# STELLA_RF.net
KiCad netlist of a schematic drawn in EAGLE
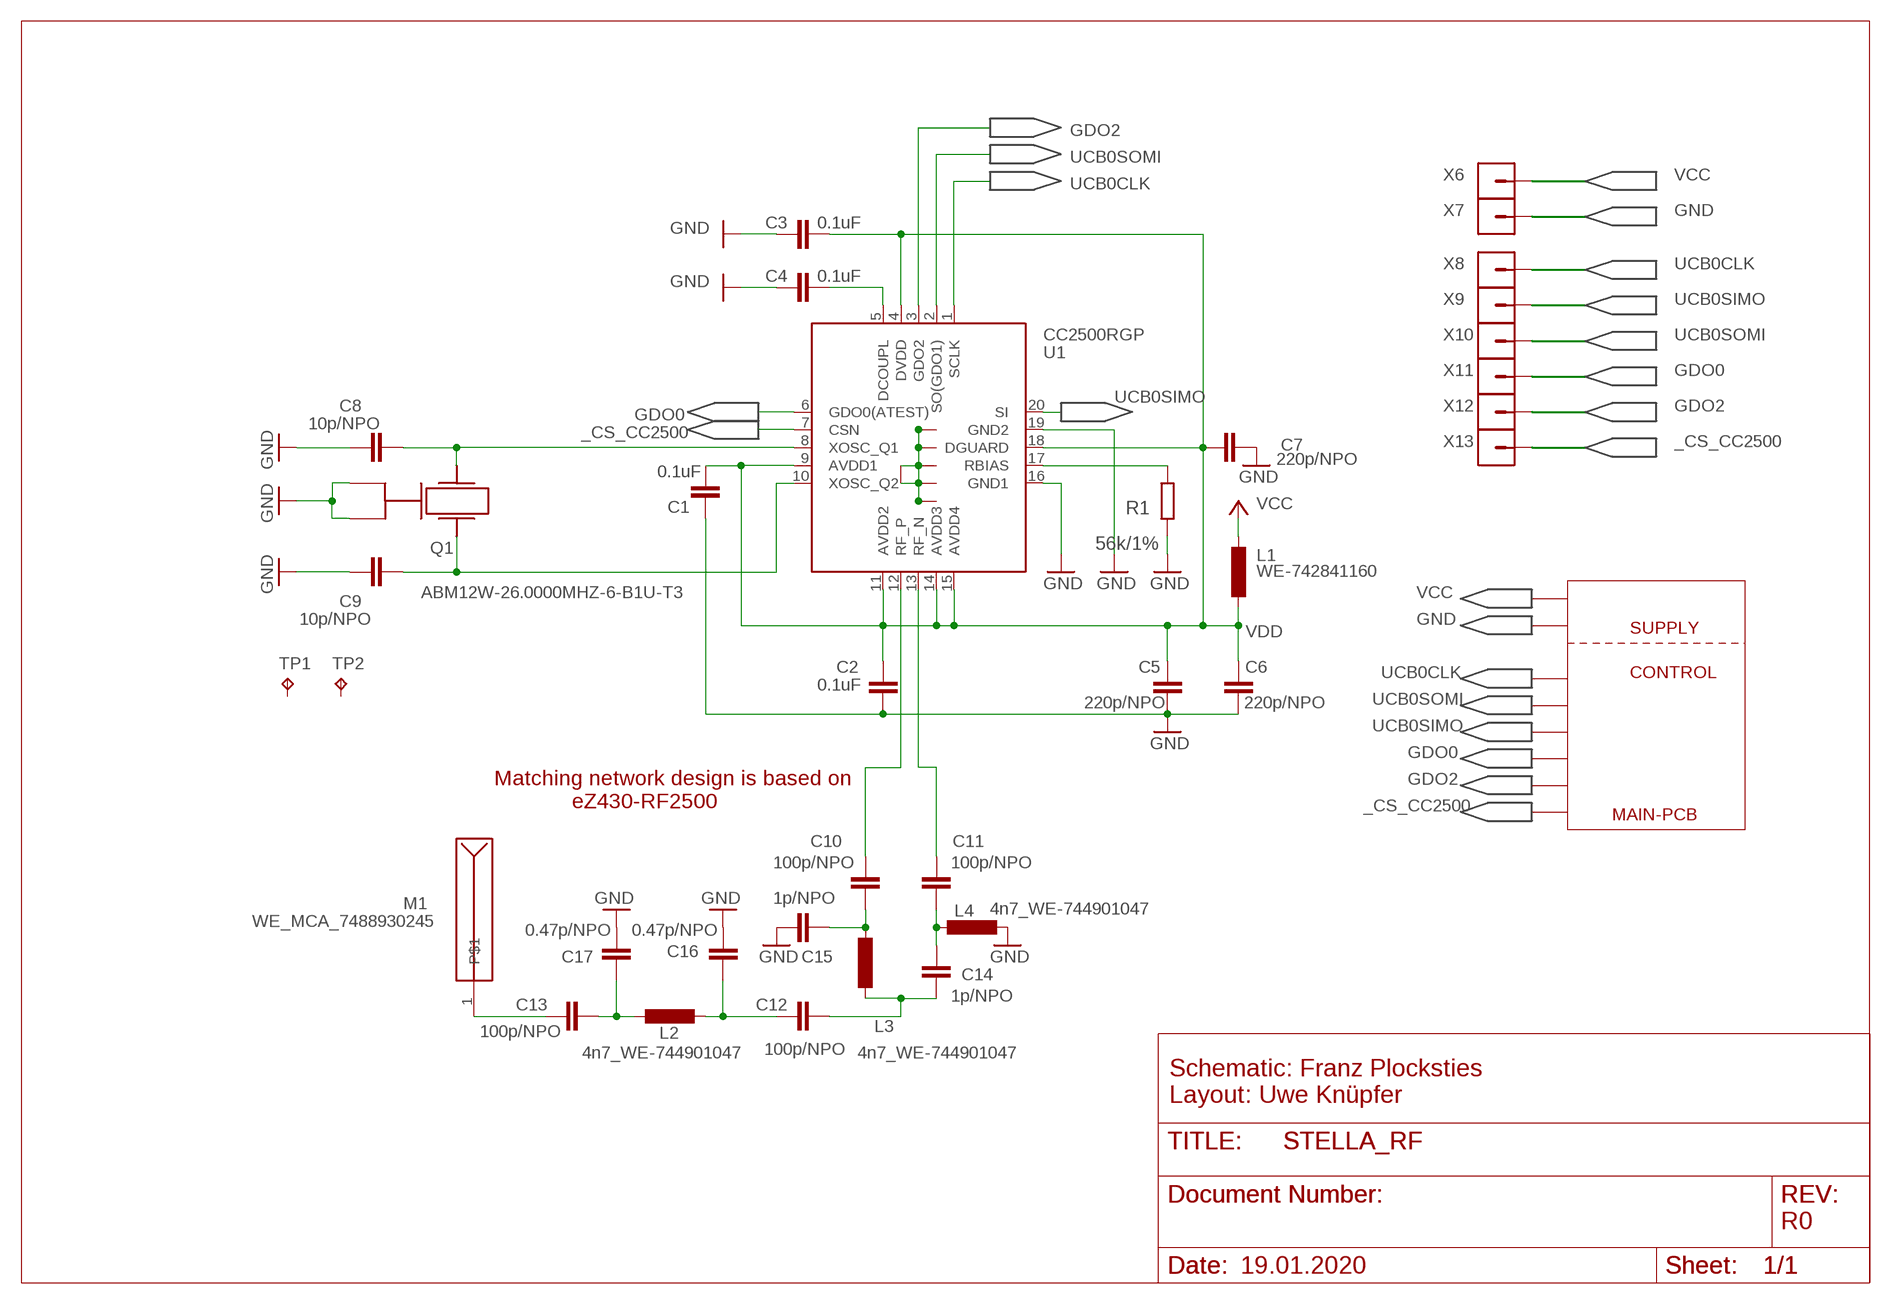
[diagram p0: schematic, sheet 1]

(export (version "E")
  (design (tool "Eeschema 10.0.6"))
  (components
    (comp (ref "C1")
      (value "0.1uF")
      (footprint "eagle-import:C0402")
      (libsource (lib "eagle-import") (part "C-EUC0402"))
    )
    (comp (ref "C2")
      (value "0.1uF")
      (footprint "eagle-import:C0402")
      (libsource (lib "eagle-import") (part "C-EUC0402"))
    )
    (comp (ref "C3")
      (value "0.1uF")
      (footprint "eagle-import:C0402")
      (libsource (lib "eagle-import") (part "C-EUC0402"))
    )
    (comp (ref "C4")
      (value "0.1uF")
      (footprint "eagle-import:C0402")
      (libsource (lib "eagle-import") (part "C-EUC0402"))
    )
    (comp (ref "C5")
      (value "220p/NPO")
      (footprint "eagle-import:C0402")
      (libsource (lib "eagle-import") (part "C-EUC0402"))
    )
    (comp (ref "C6")
      (value "220p/NPO")
      (footprint "eagle-import:C0402")
      (libsource (lib "eagle-import") (part "C-EUC0402"))
    )
    (comp (ref "C7")
      (value "220p/NPO")
      (footprint "eagle-import:C0402")
      (libsource (lib "eagle-import") (part "C-EUC0402"))
    )
    (comp (ref "C8")
      (value "10p/NPO")
      (footprint "eagle-import:C0402")
      (libsource (lib "eagle-import") (part "C-EUC0402"))
    )
    (comp (ref "C9")
      (value "10p/NPO")
      (footprint "eagle-import:C0402")
      (libsource (lib "eagle-import") (part "C-EUC0402"))
    )
    (comp (ref "C10")
      (value "100p/NPO")
      (footprint "eagle-import:C0402")
      (libsource (lib "eagle-import") (part "C-EUC0402"))
    )
    (comp (ref "C11")
      (value "100p/NPO")
      (footprint "eagle-import:C0402")
      (libsource (lib "eagle-import") (part "C-EUC0402"))
    )
    (comp (ref "C12")
      (value "100p/NPO")
      (footprint "eagle-import:C0402")
      (libsource (lib "eagle-import") (part "C-EUC0402"))
    )
    (comp (ref "C13")
      (value "100p/NPO")
      (footprint "eagle-import:C0402")
      (libsource (lib "eagle-import") (part "C-EUC0402"))
    )
    (comp (ref "C14")
      (value "1p/NPO")
      (footprint "eagle-import:C0402")
      (libsource (lib "eagle-import") (part "C-EUC0402"))
    )
    (comp (ref "C15")
      (value "1p/NPO")
      (footprint "eagle-import:C0402")
      (libsource (lib "eagle-import") (part "C-EUC0402"))
    )
    (comp (ref "C16")
      (value "0.47p/NPO")
      (footprint "eagle-import:C0402")
      (libsource (lib "eagle-import") (part "C-EUC0402"))
    )
    (comp (ref "C17")
      (value "0.47p/NPO")
      (footprint "eagle-import:C0402")
      (libsource (lib "eagle-import") (part "C-EUC0402"))
    )
    (comp (ref "L1")
      (value "WE-742841160")
      (footprint "eagle-import:L0402")
      (libsource (lib "eagle-import") (part "L-EU"))
    )
    (comp (ref "L2")
      (value "4n7_WE-744901047")
      (footprint "eagle-import:L0402")
      (libsource (lib "eagle-import") (part "L-EU"))
    )
    (comp (ref "L3")
      (value "4n7_WE-744901047")
      (footprint "eagle-import:L0402")
      (libsource (lib "eagle-import") (part "L-EU"))
    )
    (comp (ref "L4")
      (value "4n7_WE-744901047")
      (footprint "eagle-import:L0402")
      (libsource (lib "eagle-import") (part "L-EU"))
    )
    (comp (ref "M1")
      (value "WE_MCA_7488930245")
      (footprint "eagle-import:WE_MCA_7488930245")
      (libsource (lib "eagle-import") (part "WE_MCA_7488930245"))
    )
    (comp (ref "Q1")
      (value "ABM12W-26.0000MHZ-6-B1U-T3")
      (footprint "eagle-import:ABM12W")
      (libsource (lib "eagle-import") (part "ABM12W"))
    )
    (comp (ref "R1")
      (value "56k/1%")
      (footprint "eagle-import:R0402")
      (libsource (lib "eagle-import") (part "R-EU_R0402"))
    )
    (comp (ref "TP1")
      (value "TPTP06SQ")
      (footprint "eagle-import:TP06SQ")
      (libsource (lib "eagle-import") (part "TPTP06SQ"))
    )
    (comp (ref "TP2")
      (value "TPTP06SQ")
      (footprint "eagle-import:TP06SQ")
      (libsource (lib "eagle-import") (part "TPTP06SQ"))
    )
    (comp (ref "U1")
      (value "CC2500RGP")
      (footprint "eagle-import:CHIPCON_QLP20")
      (libsource (lib "eagle-import") (part "CHIPCON_CC1100"))
    )
    (comp (ref "X6")
      (value "1PIN_INTERFACE")
      (footprint "eagle-import:1PIN_INTERFACE")
      (libsource (lib "eagle-import") (part "1PIN_INTERFACE"))
    )
    (comp (ref "X7")
      (value "1PIN_INTERFACE")
      (footprint "eagle-import:1PIN_INTERFACE")
      (libsource (lib "eagle-import") (part "1PIN_INTERFACE"))
    )
    (comp (ref "X8")
      (value "1PIN_INTERFACE")
      (footprint "eagle-import:1PIN_INTERFACE")
      (libsource (lib "eagle-import") (part "1PIN_INTERFACE"))
    )
    (comp (ref "X9")
      (value "1PIN_INTERFACE")
      (footprint "eagle-import:1PIN_INTERFACE")
      (libsource (lib "eagle-import") (part "1PIN_INTERFACE"))
    )
    (comp (ref "X10")
      (value "1PIN_INTERFACE")
      (footprint "eagle-import:1PIN_INTERFACE")
      (libsource (lib "eagle-import") (part "1PIN_INTERFACE"))
    )
    (comp (ref "X11")
      (value "1PIN_INTERFACE")
      (footprint "eagle-import:1PIN_INTERFACE")
      (libsource (lib "eagle-import") (part "1PIN_INTERFACE"))
    )
    (comp (ref "X12")
      (value "1PIN_INTERFACE")
      (footprint "eagle-import:1PIN_INTERFACE")
      (libsource (lib "eagle-import") (part "1PIN_INTERFACE"))
    )
    (comp (ref "X13")
      (value "1PIN_INTERFACE")
      (footprint "eagle-import:1PIN_INTERFACE")
      (libsource (lib "eagle-import") (part "1PIN_INTERFACE"))
    )
  )
  (nets
    (net (code "1") (name "/GDO0") (class "Default")
      (node (ref "U1") (pin "6") (pinfunction "GDO0(ATEST)_6") (pintype "bidirectional"))
      (node (ref "X11") (pin "1") (pinfunction "1_1") (pintype "bidirectional"))
    )
    (net (code "2") (name "/GDO2") (class "Default")
      (node (ref "U1") (pin "3") (pinfunction "GDO2_3") (pintype "bidirectional"))
      (node (ref "X12") (pin "1") (pinfunction "1_1") (pintype "bidirectional"))
    )
    (net (code "3") (name "/UCB0CLK") (class "Default")
      (node (ref "U1") (pin "1") (pinfunction "SCLK_1") (pintype "bidirectional"))
      (node (ref "X8") (pin "1") (pinfunction "1_1") (pintype "bidirectional"))
    )
    (net (code "4") (name "/UCB0SIMO") (class "Default")
      (node (ref "U1") (pin "20") (pinfunction "SI_20") (pintype "bidirectional"))
      (node (ref "X9") (pin "1") (pinfunction "1_1") (pintype "bidirectional"))
    )
    (net (code "5") (name "/UCB0SOMI") (class "Default")
      (node (ref "U1") (pin "2") (pinfunction "SO(GDO1)_2") (pintype "bidirectional"))
      (node (ref "X10") (pin "1") (pinfunction "1_1") (pintype "bidirectional"))
    )
    (net (code "6") (name "/VDD") (class "Default")
      (node (ref "C1") (pin "2") (pinfunction "2_2") (pintype "passive"))
      (node (ref "C2") (pin "2") (pinfunction "2_2") (pintype "passive"))
      (node (ref "C3") (pin "2") (pinfunction "2_2") (pintype "passive"))
      (node (ref "C5") (pin "2") (pinfunction "2_2") (pintype "passive"))
      (node (ref "C6") (pin "2") (pinfunction "2_2") (pintype "passive"))
      (node (ref "C7") (pin "1") (pinfunction "1_1") (pintype "passive"))
      (node (ref "L1") (pin "2") (pinfunction "2_2") (pintype "passive"))
      (node (ref "U1") (pin "11") (pinfunction "AVDD2_11") (pintype "bidirectional"))
      (node (ref "U1") (pin "14") (pinfunction "AVDD3_14") (pintype "bidirectional"))
      (node (ref "U1") (pin "15") (pinfunction "AVDD4_15") (pintype "bidirectional"))
      (node (ref "U1") (pin "18") (pinfunction "DGUARD_18") (pintype "bidirectional"))
      (node (ref "U1") (pin "4") (pinfunction "DVDD_4") (pintype "bidirectional"))
      (node (ref "U1") (pin "9") (pinfunction "AVDD1_9") (pintype "bidirectional"))
    )
    (net (code "7") (name "/_CS_CC2500") (class "Default")
      (node (ref "U1") (pin "7") (pinfunction "CSN_7") (pintype "bidirectional"))
      (node (ref "X13") (pin "1") (pinfunction "1_1") (pintype "bidirectional"))
    )
    (net (code "8") (name "GND") (class "Default")
      (node (ref "C1") (pin "1") (pinfunction "1_1") (pintype "passive"))
      (node (ref "C15") (pin "2") (pinfunction "2_2") (pintype "passive"))
      (node (ref "C16") (pin "2") (pinfunction "2_2") (pintype "passive"))
      (node (ref "C17") (pin "2") (pinfunction "2_2") (pintype "passive"))
      (node (ref "C2") (pin "1") (pinfunction "1_1") (pintype "passive"))
      (node (ref "C3") (pin "1") (pinfunction "1_1") (pintype "passive"))
      (node (ref "C4") (pin "1") (pinfunction "1_1") (pintype "passive"))
      (node (ref "C5") (pin "1") (pinfunction "1_1") (pintype "passive"))
      (node (ref "C6") (pin "1") (pinfunction "1_1") (pintype "passive"))
      (node (ref "C7") (pin "2") (pinfunction "2_2") (pintype "passive"))
      (node (ref "C8") (pin "1") (pinfunction "1_1") (pintype "passive"))
      (node (ref "C9") (pin "1") (pinfunction "1_1") (pintype "passive"))
      (node (ref "L4") (pin "1") (pinfunction "1_1") (pintype "passive"))
      (node (ref "Q1") (pin "2") (pinfunction "2_2") (pintype "bidirectional"))
      (node (ref "Q1") (pin "4") (pinfunction "4_4") (pintype "bidirectional"))
      (node (ref "R1") (pin "2") (pinfunction "2_2") (pintype "passive"))
      (node (ref "U1") (pin "16") (pinfunction "GND1_16") (pintype "bidirectional"))
      (node (ref "U1") (pin "19") (pinfunction "GND2_19") (pintype "bidirectional"))
      (node (ref "U1") (pin "EP") (pinfunction "EP_EP") (pintype "bidirectional"))
      (node (ref "U1") (pin "GND1") (pinfunction "G1_GND1") (pintype "bidirectional"))
      (node (ref "U1") (pin "GND2") (pinfunction "G2_GND2") (pintype "bidirectional"))
      (node (ref "U1") (pin "GND3") (pinfunction "G3_GND3") (pintype "bidirectional"))
      (node (ref "U1") (pin "GND4") (pinfunction "G4_GND4") (pintype "bidirectional"))
      (node (ref "U1") (pin "GND5") (pinfunction "G5_GND5") (pintype "bidirectional"))
      (node (ref "X7") (pin "1") (pinfunction "1_1") (pintype "bidirectional"))
    )
    (net (code "9") (name "Net-(C10-Pad2)") (class "Default")
      (node (ref "C10") (pin "2") (pinfunction "2_2") (pintype "passive"))
      (node (ref "C15") (pin "1") (pinfunction "1_1") (pintype "passive"))
      (node (ref "L3") (pin "2") (pinfunction "2_2") (pintype "passive"))
    )
    (net (code "10") (name "Net-(C11-Pad2)") (class "Default")
      (node (ref "C11") (pin "2") (pinfunction "2_2") (pintype "passive"))
      (node (ref "C14") (pin "1") (pinfunction "1_1") (pintype "passive"))
      (node (ref "L4") (pin "2") (pinfunction "2_2") (pintype "passive"))
    )
    (net (code "11") (name "Net-(C12-Pad1)") (class "Default")
      (node (ref "C12") (pin "1") (pinfunction "1_1") (pintype "passive"))
      (node (ref "C14") (pin "2") (pinfunction "2_2") (pintype "passive"))
      (node (ref "L3") (pin "1") (pinfunction "1_1") (pintype "passive"))
    )
    (net (code "12") (name "Net-(C12-Pad2)") (class "Default")
      (node (ref "C12") (pin "2") (pinfunction "2_2") (pintype "passive"))
      (node (ref "C16") (pin "1") (pinfunction "1_1") (pintype "passive"))
      (node (ref "L2") (pin "2") (pinfunction "2_2") (pintype "passive"))
    )
    (net (code "13") (name "Net-(C13-Pad2)") (class "Default")
      (node (ref "C13") (pin "2") (pinfunction "2_2") (pintype "passive"))
      (node (ref "C17") (pin "1") (pinfunction "1_1") (pintype "passive"))
      (node (ref "L2") (pin "1") (pinfunction "1_1") (pintype "passive"))
    )
    (net (code "14") (name "Net-(M1-P$1)") (class "Default")
      (node (ref "C13") (pin "1") (pinfunction "1_1") (pintype "passive"))
      (node (ref "M1") (pin "1") (pinfunction "P$1_1") (pintype "bidirectional"))
    )
    (net (code "15") (name "Net-(U1-DCOUPL)") (class "Default")
      (node (ref "C4") (pin "2") (pinfunction "2_2") (pintype "passive"))
      (node (ref "U1") (pin "5") (pinfunction "DCOUPL_5") (pintype "bidirectional"))
    )
    (net (code "16") (name "Net-(U1-RBIAS)") (class "Default")
      (node (ref "R1") (pin "1") (pinfunction "1_1") (pintype "passive"))
      (node (ref "U1") (pin "17") (pinfunction "RBIAS_17") (pintype "bidirectional"))
    )
    (net (code "17") (name "Net-(U1-RF_N)") (class "Default")
      (node (ref "C11") (pin "1") (pinfunction "1_1") (pintype "passive"))
      (node (ref "U1") (pin "13") (pinfunction "RF_N_13") (pintype "bidirectional"))
    )
    (net (code "18") (name "Net-(U1-RF_P)") (class "Default")
      (node (ref "C10") (pin "1") (pinfunction "1_1") (pintype "passive"))
      (node (ref "U1") (pin "12") (pinfunction "RF_P_12") (pintype "bidirectional"))
    )
    (net (code "19") (name "Net-(U1-XOSC_Q1)") (class "Default")
      (node (ref "C8") (pin "2") (pinfunction "2_2") (pintype "passive"))
      (node (ref "Q1") (pin "1") (pinfunction "1_1") (pintype "bidirectional"))
      (node (ref "U1") (pin "8") (pinfunction "XOSC_Q1_8") (pintype "bidirectional"))
    )
    (net (code "20") (name "Net-(U1-XOSC_Q2)") (class "Default")
      (node (ref "C9") (pin "2") (pinfunction "2_2") (pintype "passive"))
      (node (ref "Q1") (pin "3") (pinfunction "3_3") (pintype "bidirectional"))
      (node (ref "U1") (pin "10") (pinfunction "XOSC_Q2_10") (pintype "bidirectional"))
    )
    (net (code "21") (name "VCC") (class "Default")
      (node (ref "L1") (pin "1") (pinfunction "1_1") (pintype "passive"))
      (node (ref "X6") (pin "1") (pinfunction "1_1") (pintype "bidirectional"))
    )
    (net (code "22") (name "unconnected-(TP1-PadTP)") (class "Default")
      (node (ref "TP1") (pin "TP") (pinfunction "TP_TP") (pintype "input"))
    )
    (net (code "23") (name "unconnected-(TP2-PadTP)") (class "Default")
      (node (ref "TP2") (pin "TP") (pinfunction "TP_TP") (pintype "input"))
    )
  )
)
